# Trd_pcb.net
KiCad netlist of a schematic drawn in EAGLE
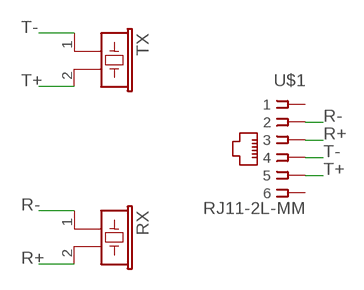
[diagram p0: schematic, sheet 1]

(export (version "E")
  (design (tool "Eeschema 10.0.6"))
  (components
    (comp (ref "RX")
      (value "EFBAA40D101")
      (footprint "eagle-import:EFBAA40D101")
      (libsource (lib "eagle-import") (part "EFB?AA40D101"))
    )
    (comp (ref "TX")
      (value "EFBAA40D101")
      (footprint "eagle-import:EFBAA40D101")
      (libsource (lib "eagle-import") (part "EFB?AA40D101"))
    )
    (comp (ref "U$1")
      (value "RJ11-2L-MM")
      (footprint "eagle-import:RJ11-NO_SHIELD_2")
      (libsource (lib "eagle-import") (part "RJ11-2L-MM"))
    )
  )
  (nets
    (net (code "1") (name "/R+") (class "Default")
      (node (ref "RX") (pin "2") (pinfunction "2_2") (pintype "passive"))
      (node (ref "U$1") (pin "3") (pinfunction "3_3") (pintype "passive"))
    )
    (net (code "2") (name "/R-") (class "Default")
      (node (ref "RX") (pin "1") (pinfunction "1_1") (pintype "passive"))
      (node (ref "U$1") (pin "2") (pinfunction "2_2") (pintype "passive"))
    )
    (net (code "3") (name "/T+") (class "Default")
      (node (ref "TX") (pin "2") (pinfunction "2_2") (pintype "passive"))
      (node (ref "U$1") (pin "5") (pinfunction "5_5") (pintype "passive"))
    )
    (net (code "4") (name "/T-") (class "Default")
      (node (ref "TX") (pin "1") (pinfunction "1_1") (pintype "passive"))
      (node (ref "U$1") (pin "4") (pinfunction "4_4") (pintype "passive"))
    )
    (net (code "5") (name "unconnected-(U$1-Pad1)") (class "Default")
      (node (ref "U$1") (pin "1") (pinfunction "1_1") (pintype "passive"))
    )
    (net (code "6") (name "unconnected-(U$1-Pad6)") (class "Default")
      (node (ref "U$1") (pin "6") (pinfunction "6_6") (pintype "passive"))
    )
  )
)
